# LCD_Connection.net
KiCad netlist of a schematic drawn in EAGLE
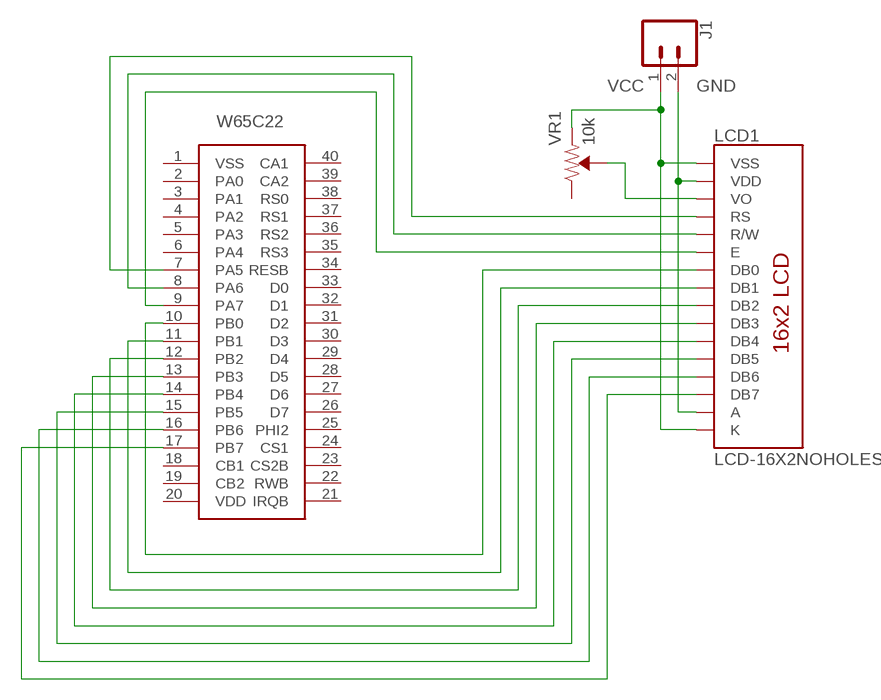
[diagram p0: schematic, sheet 1]

(export (version "E")
  (design (tool "Eeschema 10.0.6"))
  (components
    (comp (ref "J1")
      (value "CONN_02POGO_PIN_HOLES_ONLY")
      (footprint "eagle-import:1X02_PP_HOLES_ONLY")
      (libsource (lib "eagle-import") (part "CONN_02POGO_PIN_HOLES_ONLY"))
    )
    (comp (ref "LCD1")
      (value "LCD-16X2NOHOLES")
      (footprint "eagle-import:LCD-16X2_NOHOLESNOSILK")
      (libsource (lib "eagle-import") (part "LCD-16X2NOHOLES"))
    )
    (comp (ref "U$1")
      (value "W65C22")
      (footprint "eagle-import:DIP1150W53P250L4975H200Q40B")
      (libsource (lib "eagle-import") (part "W65C22"))
    )
    (comp (ref "VR1")
      (value "10k")
      (footprint "eagle-import:TRIMPOT-SMD-3MM-CLOSED")
      (libsource (lib "eagle-import") (part "TRIMPOT-SMD-3MM-CLOSED-1/8W-20%"))
    )
  )
  (nets
    (net (code "1") (name "/GND") (class "Default")
      (node (ref "J1") (pin "2") (pinfunction "2_2") (pintype "passive"))
      (node (ref "LCD1") (pin "15") (pinfunction "A_15") (pintype "power_in"))
      (node (ref "LCD1") (pin "2") (pinfunction "VDD_2") (pintype "power_in"))
    )
    (net (code "2") (name "/VCC") (class "Default")
      (node (ref "J1") (pin "1") (pinfunction "1_1") (pintype "passive"))
      (node (ref "LCD1") (pin "1") (pinfunction "VSS_1") (pintype "power_in"))
      (node (ref "LCD1") (pin "16") (pinfunction "K_16") (pintype "power_in"))
      (node (ref "VR1") (pin "1") (pinfunction "CCW_1") (pintype "passive"))
    )
    (net (code "3") (name "Net-(LCD1-DB0)") (class "Default")
      (node (ref "LCD1") (pin "7") (pinfunction "DB0_7") (pintype "bidirectional"))
      (node (ref "U$1") (pin "10") (pinfunction "PB0_10") (pintype "bidirectional"))
    )
    (net (code "4") (name "Net-(LCD1-DB1)") (class "Default")
      (node (ref "LCD1") (pin "8") (pinfunction "DB1_8") (pintype "bidirectional"))
      (node (ref "U$1") (pin "11") (pinfunction "PB1_11") (pintype "bidirectional"))
    )
    (net (code "5") (name "Net-(LCD1-DB2)") (class "Default")
      (node (ref "LCD1") (pin "9") (pinfunction "DB2_9") (pintype "bidirectional"))
      (node (ref "U$1") (pin "12") (pinfunction "PB2_12") (pintype "bidirectional"))
    )
    (net (code "6") (name "Net-(LCD1-DB3)") (class "Default")
      (node (ref "LCD1") (pin "10") (pinfunction "DB3_10") (pintype "bidirectional"))
      (node (ref "U$1") (pin "13") (pinfunction "PB3_13") (pintype "bidirectional"))
    )
    (net (code "7") (name "Net-(LCD1-DB4)") (class "Default")
      (node (ref "LCD1") (pin "11") (pinfunction "DB4_11") (pintype "bidirectional"))
      (node (ref "U$1") (pin "14") (pinfunction "PB4_14") (pintype "bidirectional"))
    )
    (net (code "8") (name "Net-(LCD1-DB5)") (class "Default")
      (node (ref "LCD1") (pin "12") (pinfunction "DB5_12") (pintype "bidirectional"))
      (node (ref "U$1") (pin "15") (pinfunction "PB5_15") (pintype "bidirectional"))
    )
    (net (code "9") (name "Net-(LCD1-DB6)") (class "Default")
      (node (ref "LCD1") (pin "13") (pinfunction "DB6_13") (pintype "bidirectional"))
      (node (ref "U$1") (pin "16") (pinfunction "PB6_16") (pintype "bidirectional"))
    )
    (net (code "10") (name "Net-(LCD1-DB7)") (class "Default")
      (node (ref "LCD1") (pin "14") (pinfunction "DB7_14") (pintype "bidirectional"))
      (node (ref "U$1") (pin "17") (pinfunction "PB7_17") (pintype "bidirectional"))
    )
    (net (code "11") (name "Net-(LCD1-E)") (class "Default")
      (node (ref "LCD1") (pin "6") (pinfunction "E_6") (pintype "input"))
      (node (ref "U$1") (pin "9") (pinfunction "PA7_9") (pintype "bidirectional"))
    )
    (net (code "12") (name "Net-(LCD1-RS)") (class "Default")
      (node (ref "LCD1") (pin "4") (pinfunction "RS_4") (pintype "input"))
      (node (ref "U$1") (pin "7") (pinfunction "PA5_7") (pintype "bidirectional"))
    )
    (net (code "13") (name "Net-(LCD1-R{slash}W)") (class "Default")
      (node (ref "LCD1") (pin "5") (pinfunction "R/W_5") (pintype "input"))
      (node (ref "U$1") (pin "8") (pinfunction "PA6_8") (pintype "bidirectional"))
    )
    (net (code "14") (name "Net-(LCD1-VO)") (class "Default")
      (node (ref "LCD1") (pin "3") (pinfunction "VO_3") (pintype "bidirectional"))
      (node (ref "VR1") (pin "2") (pinfunction "WIPER_2") (pintype "passive"))
    )
    (net (code "15") (name "unconnected-(U$1-CA1-Pad40)") (class "Default")
      (node (ref "U$1") (pin "40") (pinfunction "CA1_40") (pintype "bidirectional"))
    )
    (net (code "16") (name "unconnected-(U$1-CA2-Pad39)") (class "Default")
      (node (ref "U$1") (pin "39") (pinfunction "CA2_39") (pintype "bidirectional"))
    )
    (net (code "17") (name "unconnected-(U$1-CB1-Pad18)") (class "Default")
      (node (ref "U$1") (pin "18") (pinfunction "CB1_18") (pintype "bidirectional"))
    )
    (net (code "18") (name "unconnected-(U$1-CB2-Pad19)") (class "Default")
      (node (ref "U$1") (pin "19") (pinfunction "CB2_19") (pintype "bidirectional"))
    )
    (net (code "19") (name "unconnected-(U$1-CS1-Pad24)") (class "Default")
      (node (ref "U$1") (pin "24") (pinfunction "CS1_24") (pintype "bidirectional"))
    )
    (net (code "20") (name "unconnected-(U$1-CS2B-Pad23)") (class "Default")
      (node (ref "U$1") (pin "23") (pinfunction "CS2B_23") (pintype "bidirectional"))
    )
    (net (code "21") (name "unconnected-(U$1-D0-Pad33)") (class "Default")
      (node (ref "U$1") (pin "33") (pinfunction "D0_33") (pintype "bidirectional"))
    )
    (net (code "22") (name "unconnected-(U$1-D1-Pad32)") (class "Default")
      (node (ref "U$1") (pin "32") (pinfunction "D1_32") (pintype "bidirectional"))
    )
    (net (code "23") (name "unconnected-(U$1-D2-Pad31)") (class "Default")
      (node (ref "U$1") (pin "31") (pinfunction "D2_31") (pintype "bidirectional"))
    )
    (net (code "24") (name "unconnected-(U$1-D3-Pad30)") (class "Default")
      (node (ref "U$1") (pin "30") (pinfunction "D3_30") (pintype "bidirectional"))
    )
    (net (code "25") (name "unconnected-(U$1-D4-Pad29)") (class "Default")
      (node (ref "U$1") (pin "29") (pinfunction "D4_29") (pintype "bidirectional"))
    )
    (net (code "26") (name "unconnected-(U$1-D5-Pad28)") (class "Default")
      (node (ref "U$1") (pin "28") (pinfunction "D5_28") (pintype "bidirectional"))
    )
    (net (code "27") (name "unconnected-(U$1-D6-Pad27)") (class "Default")
      (node (ref "U$1") (pin "27") (pinfunction "D6_27") (pintype "bidirectional"))
    )
    (net (code "28") (name "unconnected-(U$1-D7-Pad26)") (class "Default")
      (node (ref "U$1") (pin "26") (pinfunction "D7_26") (pintype "bidirectional"))
    )
    (net (code "29") (name "unconnected-(U$1-IRQB-Pad21)") (class "Default")
      (node (ref "U$1") (pin "21") (pinfunction "IRQB_21") (pintype "bidirectional"))
    )
    (net (code "30") (name "unconnected-(U$1-PA0-Pad2)") (class "Default")
      (node (ref "U$1") (pin "2") (pinfunction "PA0_2") (pintype "bidirectional"))
    )
    (net (code "31") (name "unconnected-(U$1-PA1-Pad3)") (class "Default")
      (node (ref "U$1") (pin "3") (pinfunction "PA1_3") (pintype "bidirectional"))
    )
    (net (code "32") (name "unconnected-(U$1-PA2-Pad4)") (class "Default")
      (node (ref "U$1") (pin "4") (pinfunction "PA2_4") (pintype "bidirectional"))
    )
    (net (code "33") (name "unconnected-(U$1-PA3-Pad5)") (class "Default")
      (node (ref "U$1") (pin "5") (pinfunction "PA3_5") (pintype "bidirectional"))
    )
    (net (code "34") (name "unconnected-(U$1-PA4-Pad6)") (class "Default")
      (node (ref "U$1") (pin "6") (pinfunction "PA4_6") (pintype "bidirectional"))
    )
    (net (code "35") (name "unconnected-(U$1-PHI2-Pad25)") (class "Default")
      (node (ref "U$1") (pin "25") (pinfunction "PHI2_25") (pintype "bidirectional"))
    )
    (net (code "36") (name "unconnected-(U$1-RESB-Pad34)") (class "Default")
      (node (ref "U$1") (pin "34") (pinfunction "RESB_34") (pintype "bidirectional"))
    )
    (net (code "37") (name "unconnected-(U$1-RS0-Pad38)") (class "Default")
      (node (ref "U$1") (pin "38") (pinfunction "RS0_38") (pintype "bidirectional"))
    )
    (net (code "38") (name "unconnected-(U$1-RS1-Pad37)") (class "Default")
      (node (ref "U$1") (pin "37") (pinfunction "RS1_37") (pintype "bidirectional"))
    )
    (net (code "39") (name "unconnected-(U$1-RS2-Pad36)") (class "Default")
      (node (ref "U$1") (pin "36") (pinfunction "RS2_36") (pintype "bidirectional"))
    )
    (net (code "40") (name "unconnected-(U$1-RS3-Pad35)") (class "Default")
      (node (ref "U$1") (pin "35") (pinfunction "RS3_35") (pintype "bidirectional"))
    )
    (net (code "41") (name "unconnected-(U$1-RWB-Pad22)") (class "Default")
      (node (ref "U$1") (pin "22") (pinfunction "RWB_22") (pintype "bidirectional"))
    )
    (net (code "42") (name "unconnected-(U$1-VDD-Pad20)") (class "Default")
      (node (ref "U$1") (pin "20") (pinfunction "VDD_20") (pintype "bidirectional"))
    )
    (net (code "43") (name "unconnected-(U$1-VSS-Pad1)") (class "Default")
      (node (ref "U$1") (pin "1") (pinfunction "VSS_1") (pintype "bidirectional"))
    )
    (net (code "44") (name "unconnected-(VR1-CW-Pad3)") (class "Default")
      (node (ref "VR1") (pin "3") (pinfunction "CW_3") (pintype "passive"))
    )
  )
)
